# power.net
KiCad netlist of a schematic drawn in Altium Designer
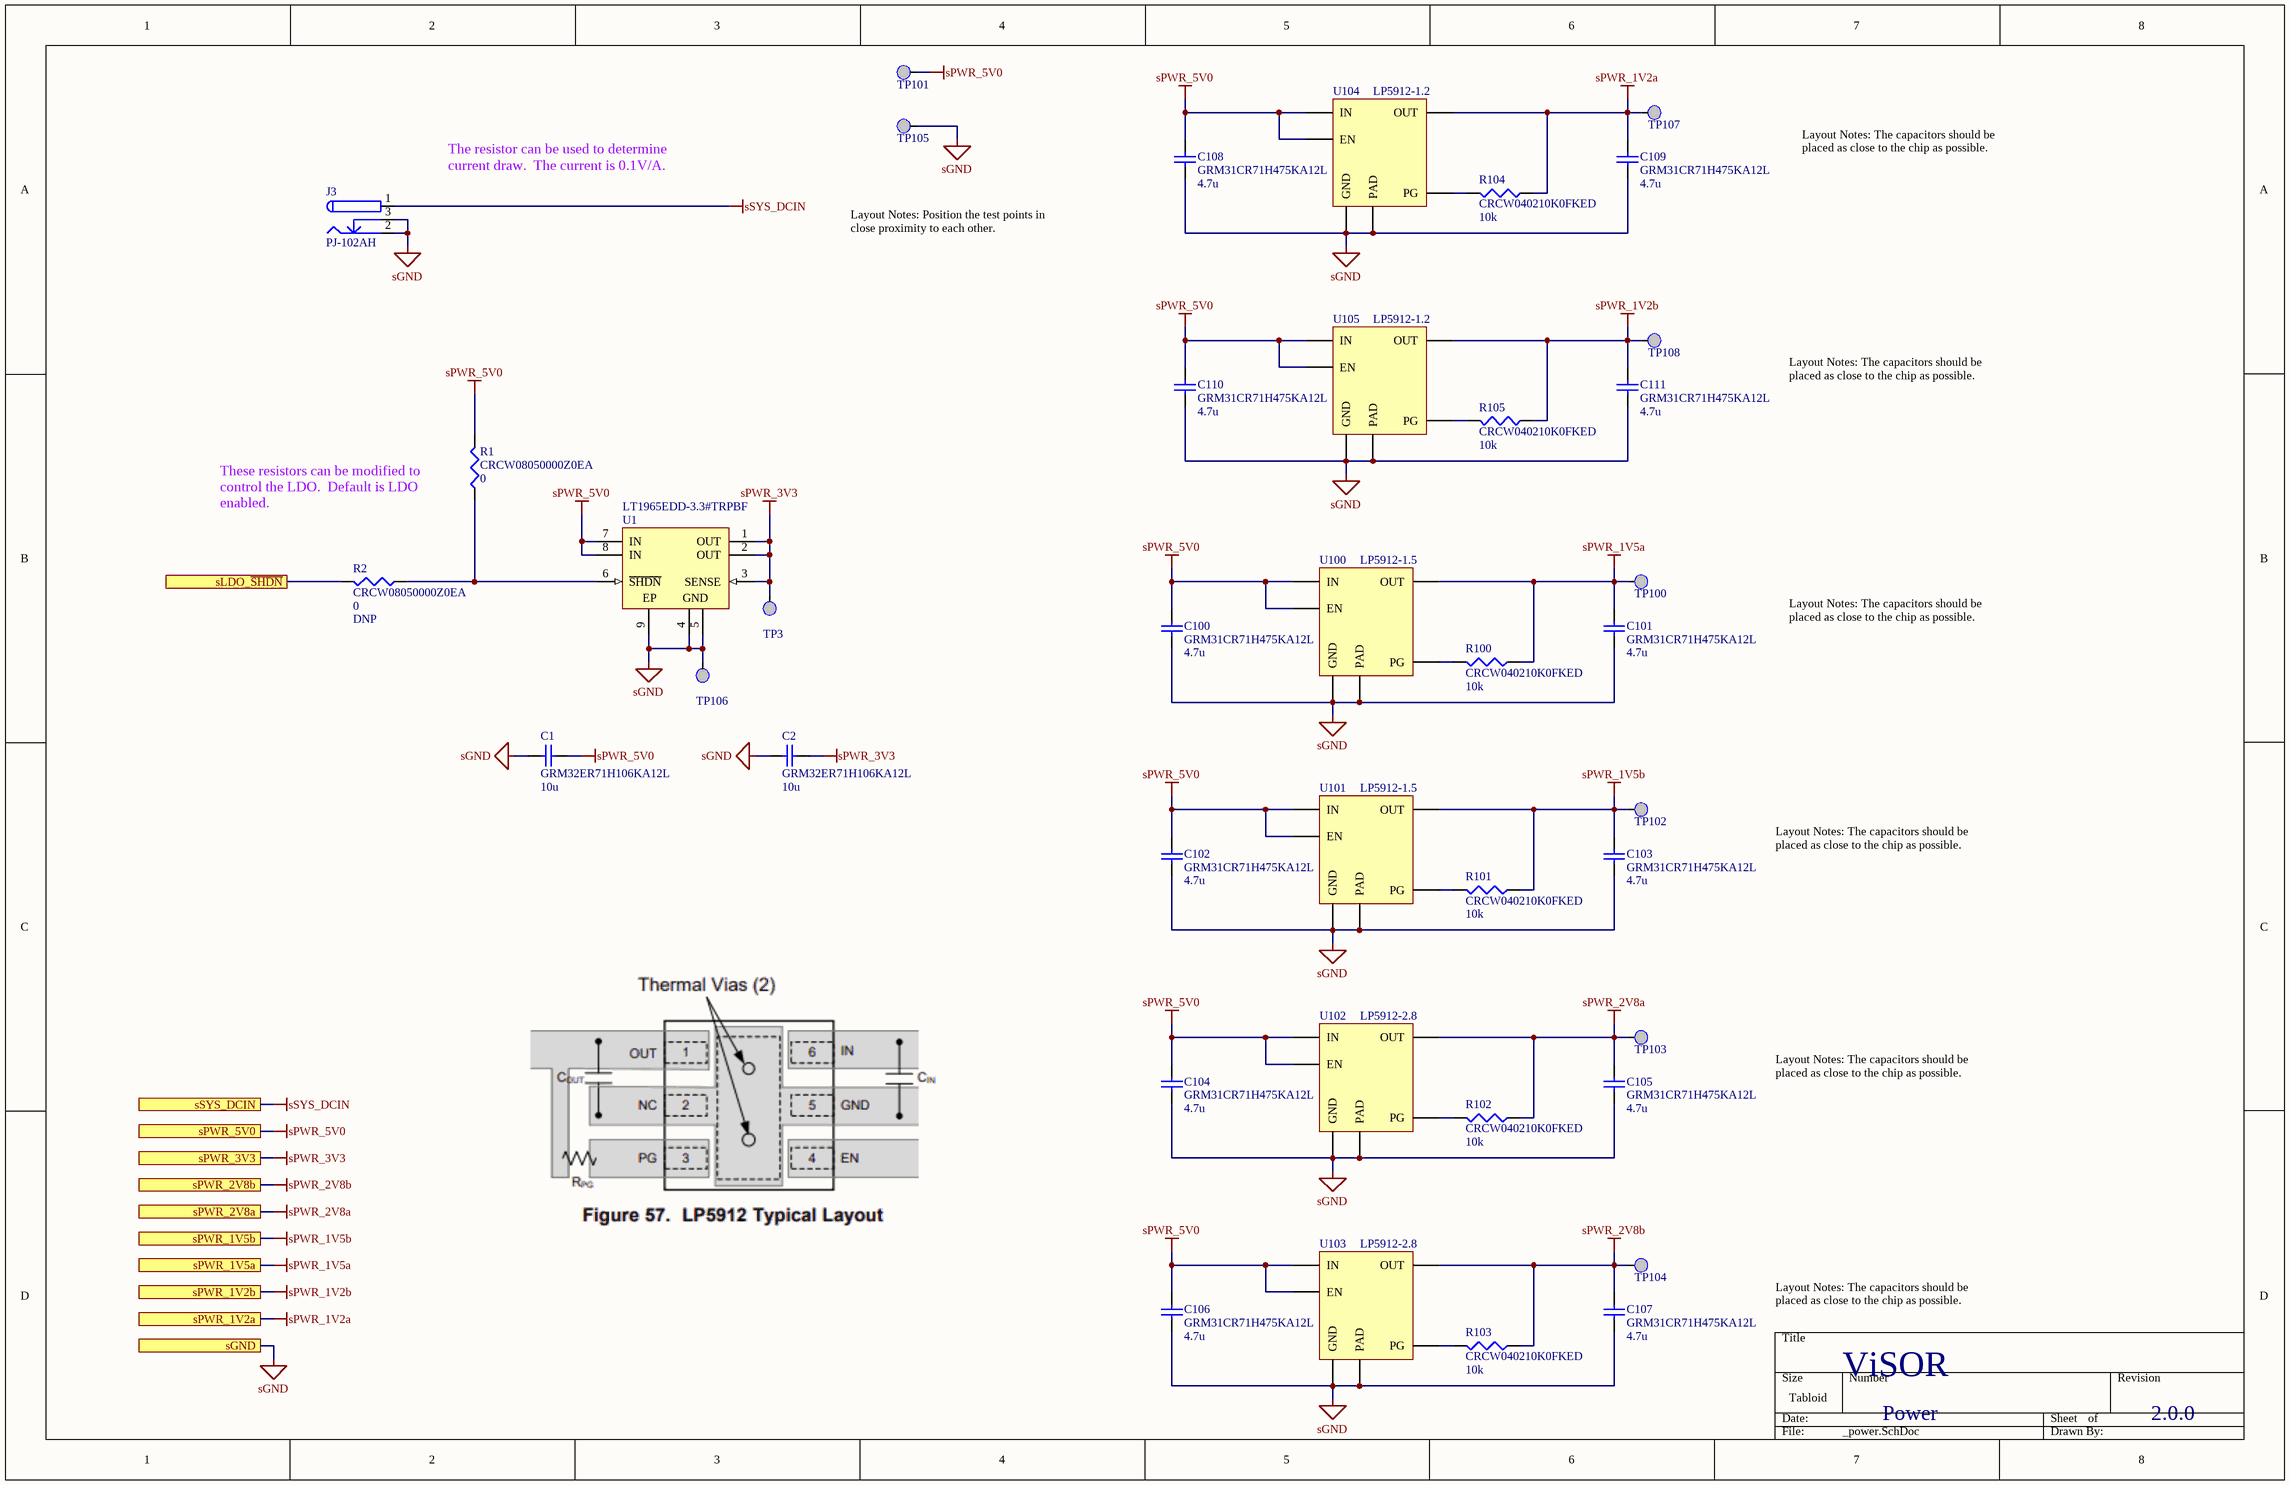
[diagram p0: _power.SchDoc]

(export (version "E")
  (design (tool "Eeschema 10.0.6"))
  (components
    (comp (ref "C1")
      (value "GRM32ER71H106KA12L")
      (footprint "1210")
      (description "-55-125C, 1005, 50V, X7R, ±10%")
      (fields (field (name "ALTIUM_VALUE") "10u"))
      (libsource (lib "standard_capacitors") (part "GRM32ER71HxxxKdddd"))
    )
    (comp (ref "C2")
      (value "GRM32ER71H106KA12L")
      (footprint "1210")
      (description "-55-125C, 1005, 50V, X7R, ±10%")
      (fields (field (name "ALTIUM_VALUE") "10u"))
      (libsource (lib "standard_capacitors") (part "GRM32ER71HxxxKdddd"))
    )
    (comp (ref "C100")
      (value "GRM31CR71H475KA12L")
      (footprint "1206")
      (description "-55-125C, 3216, 50V, X7R, ±10%")
      (fields (field (name "ALTIUM_VALUE") "4.7u"))
      (libsource (lib "standard_capacitors") (part "GRM31CR71HxxxKdddd"))
    )
    (comp (ref "C101")
      (value "GRM31CR71H475KA12L")
      (footprint "1206")
      (description "-55-125C, 3216, 50V, X7R, ±10%")
      (fields (field (name "ALTIUM_VALUE") "4.7u"))
      (libsource (lib "standard_capacitors") (part "GRM31CR71HxxxKdddd"))
    )
    (comp (ref "C102")
      (value "GRM31CR71H475KA12L")
      (footprint "1206")
      (description "-55-125C, 3216, 50V, X7R, ±10%")
      (fields (field (name "ALTIUM_VALUE") "4.7u"))
      (libsource (lib "standard_capacitors") (part "GRM31CR71HxxxKdddd"))
    )
    (comp (ref "C103")
      (value "GRM31CR71H475KA12L")
      (footprint "1206")
      (description "-55-125C, 3216, 50V, X7R, ±10%")
      (fields (field (name "ALTIUM_VALUE") "4.7u"))
      (libsource (lib "standard_capacitors") (part "GRM31CR71HxxxKdddd"))
    )
    (comp (ref "C104")
      (value "GRM31CR71H475KA12L")
      (footprint "1206")
      (description "-55-125C, 3216, 50V, X7R, ±10%")
      (fields (field (name "ALTIUM_VALUE") "4.7u"))
      (libsource (lib "standard_capacitors") (part "GRM31CR71HxxxKdddd"))
    )
    (comp (ref "C105")
      (value "GRM31CR71H475KA12L")
      (footprint "1206")
      (description "-55-125C, 3216, 50V, X7R, ±10%")
      (fields (field (name "ALTIUM_VALUE") "4.7u"))
      (libsource (lib "standard_capacitors") (part "GRM31CR71HxxxKdddd"))
    )
    (comp (ref "C106")
      (value "GRM31CR71H475KA12L")
      (footprint "1206")
      (description "-55-125C, 3216, 50V, X7R, ±10%")
      (fields (field (name "ALTIUM_VALUE") "4.7u"))
      (libsource (lib "standard_capacitors") (part "GRM31CR71HxxxKdddd"))
    )
    (comp (ref "C107")
      (value "GRM31CR71H475KA12L")
      (footprint "1206")
      (description "-55-125C, 3216, 50V, X7R, ±10%")
      (fields (field (name "ALTIUM_VALUE") "4.7u"))
      (libsource (lib "standard_capacitors") (part "GRM31CR71HxxxKdddd"))
    )
    (comp (ref "C108")
      (value "GRM31CR71H475KA12L")
      (footprint "1206")
      (description "-55-125C, 3216, 50V, X7R, ±10%")
      (fields (field (name "ALTIUM_VALUE") "4.7u"))
      (libsource (lib "standard_capacitors") (part "GRM31CR71HxxxKdddd"))
    )
    (comp (ref "C109")
      (value "GRM31CR71H475KA12L")
      (footprint "1206")
      (description "-55-125C, 3216, 50V, X7R, ±10%")
      (fields (field (name "ALTIUM_VALUE") "4.7u"))
      (libsource (lib "standard_capacitors") (part "GRM31CR71HxxxKdddd"))
    )
    (comp (ref "C110")
      (value "GRM31CR71H475KA12L")
      (footprint "1206")
      (description "-55-125C, 3216, 50V, X7R, ±10%")
      (fields (field (name "ALTIUM_VALUE") "4.7u"))
      (libsource (lib "standard_capacitors") (part "GRM31CR71HxxxKdddd"))
    )
    (comp (ref "C111")
      (value "GRM31CR71H475KA12L")
      (footprint "1206")
      (description "-55-125C, 3216, 50V, X7R, ±10%")
      (fields (field (name "ALTIUM_VALUE") "4.7u"))
      (libsource (lib "standard_capacitors") (part "GRM31CR71HxxxKdddd"))
    )
    (comp (ref "J3")
      (value "PJ-102AH")
      (footprint "PJ-102AH")
      (description "Low Voltage Power Supply Connector, 2.1 mm")
      (libsource (lib "cui") (part "PJ-102AH"))
    )
    (comp (ref "R1")
      (value "CRCW08050000Z0EA")
      (footprint "6-0805_M")
      (description "0Ω Resistor")
      (fields (field (name "ALTIUM_VALUE") "0") (field (name "PUBLISHER") "Altium Limited"))
      (libsource (lib "miscellaneous_devices") (part "Res3"))
    )
    (comp (ref "R2")
      (value "CRCW08050000Z0EA")
      (footprint "6-0805_M")
      (description "0Ω Resistor")
      (fields
        (field (name "ALTIUM_VALUE") "0")
        (field (name "ALTIUM_UNNAMED_1") "DNP")
        (field (name "PUBLISHER") "Altium Limited")
      )
      (libsource (lib "miscellaneous_devices") (part "Res3"))
    )
    (comp (ref "R100")
      (value "CRCW040210K0FKED")
      (footprint "0402")
      (description "0.125W, -55-155C, 1005, 50V, ±1%")
      (fields (field (name "ALTIUM_VALUE") "10k"))
      (libsource (lib "standard_resistors") (part "CRCW0402xxxxFKED"))
    )
    (comp (ref "R101")
      (value "CRCW040210K0FKED")
      (footprint "0402")
      (description "0.125W, -55-155C, 1005, 50V, ±1%")
      (fields (field (name "ALTIUM_VALUE") "10k"))
      (libsource (lib "standard_resistors") (part "CRCW0402xxxxFKED"))
    )
    (comp (ref "R102")
      (value "CRCW040210K0FKED")
      (footprint "0402")
      (description "0.125W, -55-155C, 1005, 50V, ±1%")
      (fields (field (name "ALTIUM_VALUE") "10k"))
      (libsource (lib "standard_resistors") (part "CRCW0402xxxxFKED"))
    )
    (comp (ref "R103")
      (value "CRCW040210K0FKED")
      (footprint "0402")
      (description "0.125W, -55-155C, 1005, 50V, ±1%")
      (fields (field (name "ALTIUM_VALUE") "10k"))
      (libsource (lib "standard_resistors") (part "CRCW0402xxxxFKED"))
    )
    (comp (ref "R104")
      (value "CRCW040210K0FKED")
      (footprint "0402")
      (description "0.125W, -55-155C, 1005, 50V, ±1%")
      (fields (field (name "ALTIUM_VALUE") "10k"))
      (libsource (lib "standard_resistors") (part "CRCW0402xxxxFKED"))
    )
    (comp (ref "R105")
      (value "CRCW040210K0FKED")
      (footprint "0402")
      (description "0.125W, -55-155C, 1005, 50V, ±1%")
      (fields (field (name "ALTIUM_VALUE") "10k"))
      (libsource (lib "standard_resistors") (part "CRCW0402xxxxFKED"))
    )
    (comp (ref "TP3") (value "TP") (footprint "TP_TH") (libsource (lib "common") (part "TP")))
    (comp (ref "TP100") (value "TP") (footprint "TP_TH") (libsource (lib "common") (part "TP")))
    (comp (ref "TP101") (value "TP") (footprint "TP_TH") (libsource (lib "common") (part "TP")))
    (comp (ref "TP102") (value "TP") (footprint "TP_TH") (libsource (lib "common") (part "TP")))
    (comp (ref "TP103") (value "TP") (footprint "TP_TH") (libsource (lib "common") (part "TP")))
    (comp (ref "TP104") (value "TP") (footprint "TP_TH") (libsource (lib "common") (part "TP")))
    (comp (ref "TP105") (value "TP") (footprint "TP_TH") (libsource (lib "common") (part "TP")))
    (comp (ref "TP106") (value "TP") (footprint "TP_TH") (libsource (lib "common") (part "TP")))
    (comp (ref "TP107") (value "TP") (footprint "TP_TH") (libsource (lib "common") (part "TP")))
    (comp (ref "TP108") (value "TP") (footprint "TP_TH") (libsource (lib "common") (part "TP")))
    (comp (ref "U1")
      (value "LT1965EDD-3.3#TRPBF")
      (footprint "LT-DD-8_V - MOD")
      (fields (field (name "MANUFACTURER") "Linear Technology"))
      (libsource (lib "linear_technology") (part "LT1965EDD-3.3#TRPBF"))
    )
    (comp (ref "U100")
      (value "LP5912-1.5")
      (footprint "DRV0006A")
      (description "500-mA Low-Noise, Low-IQ LDO")
      (libsource (lib "texas_instruments") (part "LP5912-x.x"))
    )
    (comp (ref "U101")
      (value "LP5912-1.5")
      (footprint "DRV0006A")
      (description "500-mA Low-Noise, Low-IQ LDO")
      (libsource (lib "texas_instruments") (part "LP5912-x.x"))
    )
    (comp (ref "U102")
      (value "LP5912-2.8")
      (footprint "DRV0006A")
      (description "500-mA Low-Noise, Low-IQ LDO")
      (libsource (lib "texas_instruments") (part "LP5912-x.x"))
    )
    (comp (ref "U103")
      (value "LP5912-2.8")
      (footprint "DRV0006A")
      (description "500-mA Low-Noise, Low-IQ LDO")
      (libsource (lib "texas_instruments") (part "LP5912-x.x"))
    )
    (comp (ref "U104")
      (value "LP5912-1.2")
      (footprint "DRV0006A")
      (description "500-mA Low-Noise, Low-IQ LDO")
      (libsource (lib "texas_instruments") (part "LP5912-x.x"))
    )
    (comp (ref "U105")
      (value "LP5912-1.2")
      (footprint "DRV0006A")
      (description "500-mA Low-Noise, Low-IQ LDO")
      (libsource (lib "texas_instruments") (part "LP5912-x.x"))
    )
  )
  (nets
    (net (code "1") (name "/sLDO_~{SHDN}") (class "Default")
      (node (ref "R2") (pin "2") (pinfunction "2_2") (pintype "passive"))
    )
    (net (code "2") (name "Net-(U1-~{SHDN})") (class "Default")
      (node (ref "R1") (pin "1") (pinfunction "1_1") (pintype "passive"))
      (node (ref "R2") (pin "1") (pinfunction "1_1") (pintype "passive"))
      (node (ref "U1") (pin "6") (pinfunction "~{SHDN}_6") (pintype "input"))
    )
    (net (code "3") (name "Net-(U100-PG)") (class "Default")
      (node (ref "R100") (pin "2") (pinfunction "2_2") (pintype "passive"))
      (node (ref "U100") (pin "3") (pinfunction "PG_3") (pintype "passive"))
    )
    (net (code "4") (name "Net-(U101-PG)") (class "Default")
      (node (ref "R101") (pin "2") (pinfunction "2_2") (pintype "passive"))
      (node (ref "U101") (pin "3") (pinfunction "PG_3") (pintype "passive"))
    )
    (net (code "5") (name "Net-(U102-PG)") (class "Default")
      (node (ref "R102") (pin "2") (pinfunction "2_2") (pintype "passive"))
      (node (ref "U102") (pin "3") (pinfunction "PG_3") (pintype "passive"))
    )
    (net (code "6") (name "Net-(U103-PG)") (class "Default")
      (node (ref "R103") (pin "2") (pinfunction "2_2") (pintype "passive"))
      (node (ref "U103") (pin "3") (pinfunction "PG_3") (pintype "passive"))
    )
    (net (code "7") (name "Net-(U104-PG)") (class "Default")
      (node (ref "R104") (pin "2") (pinfunction "2_2") (pintype "passive"))
      (node (ref "U104") (pin "3") (pinfunction "PG_3") (pintype "passive"))
    )
    (net (code "8") (name "Net-(U105-PG)") (class "Default")
      (node (ref "R105") (pin "2") (pinfunction "2_2") (pintype "passive"))
      (node (ref "U105") (pin "3") (pinfunction "PG_3") (pintype "passive"))
    )
    (net (code "9") (name "sGND") (class "Default")
      (node (ref "C1") (pin "1") (pinfunction "1_1") (pintype "passive"))
      (node (ref "C100") (pin "1") (pinfunction "1_1") (pintype "passive"))
      (node (ref "C101") (pin "1") (pinfunction "1_1") (pintype "passive"))
      (node (ref "C102") (pin "1") (pinfunction "1_1") (pintype "passive"))
      (node (ref "C103") (pin "1") (pinfunction "1_1") (pintype "passive"))
      (node (ref "C104") (pin "1") (pinfunction "1_1") (pintype "passive"))
      (node (ref "C105") (pin "1") (pinfunction "1_1") (pintype "passive"))
      (node (ref "C106") (pin "1") (pinfunction "1_1") (pintype "passive"))
      (node (ref "C107") (pin "1") (pinfunction "1_1") (pintype "passive"))
      (node (ref "C108") (pin "1") (pinfunction "1_1") (pintype "passive"))
      (node (ref "C109") (pin "1") (pinfunction "1_1") (pintype "passive"))
      (node (ref "C110") (pin "1") (pinfunction "1_1") (pintype "passive"))
      (node (ref "C111") (pin "1") (pinfunction "1_1") (pintype "passive"))
      (node (ref "C2") (pin "1") (pinfunction "1_1") (pintype "passive"))
      (node (ref "J3") (pin "2") (pinfunction "2_2") (pintype "power_in"))
      (node (ref "J3") (pin "3") (pinfunction "3_3") (pintype "power_in"))
      (node (ref "TP105") (pin "1") (pinfunction "1_1") (pintype "passive"))
      (node (ref "TP106") (pin "1") (pinfunction "1_1") (pintype "passive"))
      (node (ref "U1") (pin "4") (pinfunction "GND_4") (pintype "power_in"))
      (node (ref "U1") (pin "5") (pinfunction "GND_5") (pintype "power_in"))
      (node (ref "U1") (pin "9") (pinfunction "EP_9") (pintype "power_in"))
      (node (ref "U100") (pin "5") (pinfunction "GND_5") (pintype "passive"))
      (node (ref "U100") (pin "7") (pinfunction "PAD_7") (pintype "passive"))
      (node (ref "U101") (pin "5") (pinfunction "GND_5") (pintype "passive"))
      (node (ref "U101") (pin "7") (pinfunction "PAD_7") (pintype "passive"))
      (node (ref "U102") (pin "5") (pinfunction "GND_5") (pintype "passive"))
      (node (ref "U102") (pin "7") (pinfunction "PAD_7") (pintype "passive"))
      (node (ref "U103") (pin "5") (pinfunction "GND_5") (pintype "passive"))
      (node (ref "U103") (pin "7") (pinfunction "PAD_7") (pintype "passive"))
      (node (ref "U104") (pin "5") (pinfunction "GND_5") (pintype "passive"))
      (node (ref "U104") (pin "7") (pinfunction "PAD_7") (pintype "passive"))
      (node (ref "U105") (pin "5") (pinfunction "GND_5") (pintype "passive"))
      (node (ref "U105") (pin "7") (pinfunction "PAD_7") (pintype "passive"))
    )
    (net (code "10") (name "sPWR_1V2a") (class "Default")
      (node (ref "C109") (pin "2") (pinfunction "2_2") (pintype "passive"))
      (node (ref "R104") (pin "1") (pinfunction "1_1") (pintype "passive"))
      (node (ref "TP107") (pin "1") (pinfunction "1_1") (pintype "passive"))
      (node (ref "U104") (pin "1") (pinfunction "OUT_1") (pintype "passive"))
    )
    (net (code "11") (name "sPWR_1V2b") (class "Default")
      (node (ref "C111") (pin "2") (pinfunction "2_2") (pintype "passive"))
      (node (ref "R105") (pin "1") (pinfunction "1_1") (pintype "passive"))
      (node (ref "TP108") (pin "1") (pinfunction "1_1") (pintype "passive"))
      (node (ref "U105") (pin "1") (pinfunction "OUT_1") (pintype "passive"))
    )
    (net (code "12") (name "sPWR_1V5a") (class "Default")
      (node (ref "C101") (pin "2") (pinfunction "2_2") (pintype "passive"))
      (node (ref "R100") (pin "1") (pinfunction "1_1") (pintype "passive"))
      (node (ref "TP100") (pin "1") (pinfunction "1_1") (pintype "passive"))
      (node (ref "U100") (pin "1") (pinfunction "OUT_1") (pintype "passive"))
    )
    (net (code "13") (name "sPWR_1V5b") (class "Default")
      (node (ref "C103") (pin "2") (pinfunction "2_2") (pintype "passive"))
      (node (ref "R101") (pin "1") (pinfunction "1_1") (pintype "passive"))
      (node (ref "TP102") (pin "1") (pinfunction "1_1") (pintype "passive"))
      (node (ref "U101") (pin "1") (pinfunction "OUT_1") (pintype "passive"))
    )
    (net (code "14") (name "sPWR_2V8a") (class "Default")
      (node (ref "C105") (pin "2") (pinfunction "2_2") (pintype "passive"))
      (node (ref "R102") (pin "1") (pinfunction "1_1") (pintype "passive"))
      (node (ref "TP103") (pin "1") (pinfunction "1_1") (pintype "passive"))
      (node (ref "U102") (pin "1") (pinfunction "OUT_1") (pintype "passive"))
    )
    (net (code "15") (name "sPWR_2V8b") (class "Default")
      (node (ref "C107") (pin "2") (pinfunction "2_2") (pintype "passive"))
      (node (ref "R103") (pin "1") (pinfunction "1_1") (pintype "passive"))
      (node (ref "TP104") (pin "1") (pinfunction "1_1") (pintype "passive"))
      (node (ref "U103") (pin "1") (pinfunction "OUT_1") (pintype "passive"))
    )
    (net (code "16") (name "sPWR_3V3") (class "Default")
      (node (ref "C2") (pin "2") (pinfunction "2_2") (pintype "passive"))
      (node (ref "TP3") (pin "1") (pinfunction "1_1") (pintype "passive"))
      (node (ref "U1") (pin "1") (pinfunction "OUT_1") (pintype "power_in"))
      (node (ref "U1") (pin "2") (pinfunction "OUT_2") (pintype "power_in"))
      (node (ref "U1") (pin "3") (pinfunction "SENSE_3") (pintype "input"))
    )
    (net (code "17") (name "sPWR_5V0") (class "Default")
      (node (ref "C1") (pin "2") (pinfunction "2_2") (pintype "passive"))
      (node (ref "C100") (pin "2") (pinfunction "2_2") (pintype "passive"))
      (node (ref "C102") (pin "2") (pinfunction "2_2") (pintype "passive"))
      (node (ref "C104") (pin "2") (pinfunction "2_2") (pintype "passive"))
      (node (ref "C106") (pin "2") (pinfunction "2_2") (pintype "passive"))
      (node (ref "C108") (pin "2") (pinfunction "2_2") (pintype "passive"))
      (node (ref "C110") (pin "2") (pinfunction "2_2") (pintype "passive"))
      (node (ref "R1") (pin "2") (pinfunction "2_2") (pintype "passive"))
      (node (ref "TP101") (pin "1") (pinfunction "1_1") (pintype "passive"))
      (node (ref "U1") (pin "7") (pinfunction "IN_7") (pintype "power_in"))
      (node (ref "U1") (pin "8") (pinfunction "IN_8") (pintype "power_in"))
      (node (ref "U100") (pin "4") (pinfunction "EN_4") (pintype "passive"))
      (node (ref "U100") (pin "6") (pinfunction "IN_6") (pintype "passive"))
      (node (ref "U101") (pin "4") (pinfunction "EN_4") (pintype "passive"))
      (node (ref "U101") (pin "6") (pinfunction "IN_6") (pintype "passive"))
      (node (ref "U102") (pin "4") (pinfunction "EN_4") (pintype "passive"))
      (node (ref "U102") (pin "6") (pinfunction "IN_6") (pintype "passive"))
      (node (ref "U103") (pin "4") (pinfunction "EN_4") (pintype "passive"))
      (node (ref "U103") (pin "6") (pinfunction "IN_6") (pintype "passive"))
      (node (ref "U104") (pin "4") (pinfunction "EN_4") (pintype "passive"))
      (node (ref "U104") (pin "6") (pinfunction "IN_6") (pintype "passive"))
      (node (ref "U105") (pin "4") (pinfunction "EN_4") (pintype "passive"))
      (node (ref "U105") (pin "6") (pinfunction "IN_6") (pintype "passive"))
    )
    (net (code "18") (name "sSYS_DCIN") (class "Default")
      (node (ref "J3") (pin "1") (pinfunction "1_1") (pintype "power_in"))
    )
  )
)
